# TPS61200.net
KiCad netlist of a schematic drawn in EAGLE
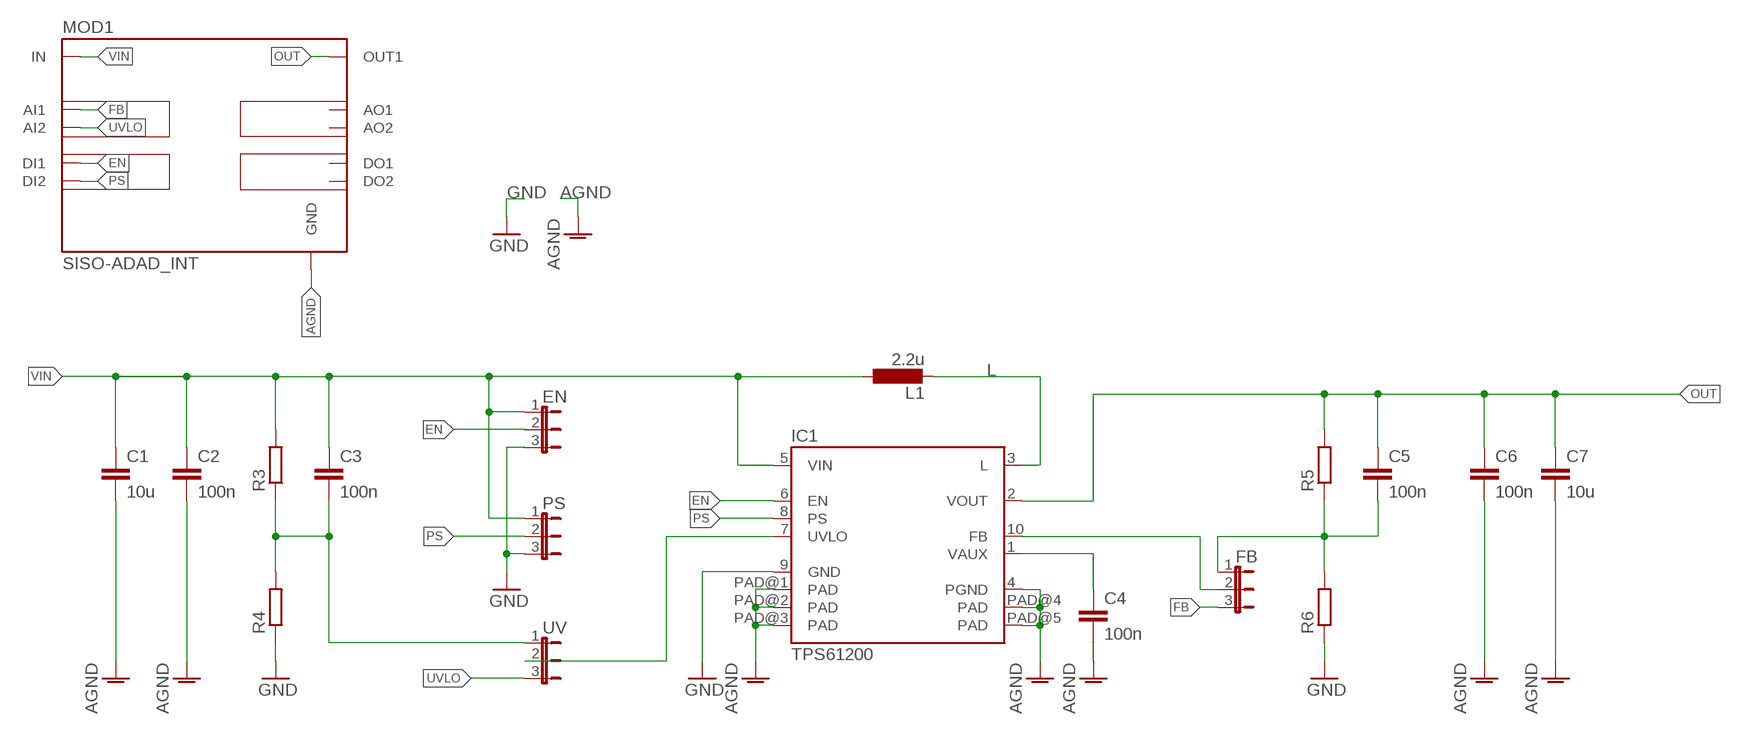
[diagram p0: schematic, sheet 1]

(export (version "E")
  (design (tool "Eeschema 10.0.6"))
  (components
    (comp (ref "C1")
      (value "10u")
      (footprint "eagle-import:C0805")
      (libsource (lib "eagle-import") (part "C-EUC0805"))
    )
    (comp (ref "C2")
      (value "100n")
      (footprint "eagle-import:C0805")
      (libsource (lib "eagle-import") (part "C-EUC0805"))
    )
    (comp (ref "C3")
      (value "100n")
      (footprint "eagle-import:C0805")
      (libsource (lib "eagle-import") (part "C-EUC0805"))
    )
    (comp (ref "C4")
      (value "100n")
      (footprint "eagle-import:C0805")
      (libsource (lib "eagle-import") (part "C-EUC0805"))
    )
    (comp (ref "C5")
      (value "100n")
      (footprint "eagle-import:C0805")
      (libsource (lib "eagle-import") (part "C-EUC0805"))
    )
    (comp (ref "C6")
      (value "100n")
      (footprint "eagle-import:C0805")
      (libsource (lib "eagle-import") (part "C-EUC0805"))
    )
    (comp (ref "C7")
      (value "10u")
      (footprint "eagle-import:C0805")
      (libsource (lib "eagle-import") (part "C-EUC0805"))
    )
    (comp (ref "EN")
      (value "JP2E")
      (footprint "eagle-import:JP2")
      (libsource (lib "eagle-import") (part "JP2E"))
    )
    (comp (ref "FB")
      (value "JP2E")
      (footprint "eagle-import:JP2")
      (libsource (lib "eagle-import") (part "JP2E"))
    )
    (comp (ref "IC1")
      (value "TPS61200")
      (footprint "eagle-import:QFN_10_PAD")
      (libsource (lib "eagle-import") (part "TPS61200"))
    )
    (comp (ref "L1")
      (value "2.2u")
      (footprint "eagle-import:L4035M")
      (libsource (lib "eagle-import") (part "L-EUL4035M"))
    )
    (comp (ref "MOD1")
      (value "SISO-ADAD_INT")
      (footprint "eagle-import:SISO-ADAD")
      (libsource (lib "eagle-import") (part "SISO-ADAD_INT"))
    )
    (comp (ref "PS")
      (value "JP2E")
      (footprint "eagle-import:JP2")
      (libsource (lib "eagle-import") (part "JP2E"))
    )
    (comp (ref "R3")
      (value "R-EU_R0805")
      (footprint "eagle-import:R0805")
      (libsource (lib "eagle-import") (part "R-EU_R0805"))
    )
    (comp (ref "R4")
      (value "R-EU_R0805")
      (footprint "eagle-import:R0805")
      (libsource (lib "eagle-import") (part "R-EU_R0805"))
    )
    (comp (ref "R5")
      (value "R-EU_R0805")
      (footprint "eagle-import:R0805")
      (libsource (lib "eagle-import") (part "R-EU_R0805"))
    )
    (comp (ref "R6")
      (value "R-EU_R0805")
      (footprint "eagle-import:R0805")
      (libsource (lib "eagle-import") (part "R-EU_R0805"))
    )
    (comp (ref "UV")
      (value "JP2E")
      (footprint "eagle-import:JP2")
      (libsource (lib "eagle-import") (part "JP2E"))
    )
  )
  (nets
    (net (code "1") (name "/L") (class "Default")
      (node (ref "IC1") (pin "3") (pinfunction "L_3") (pintype "passive"))
      (node (ref "L1") (pin "2") (pinfunction "2_2") (pintype "passive"))
    )
    (net (code "2") (name "AGND") (class "Default")
      (node (ref "C1") (pin "2") (pinfunction "2_2") (pintype "passive"))
      (node (ref "C2") (pin "2") (pinfunction "2_2") (pintype "passive"))
      (node (ref "C4") (pin "2") (pinfunction "2_2") (pintype "passive"))
      (node (ref "C6") (pin "2") (pinfunction "2_2") (pintype "passive"))
      (node (ref "C7") (pin "2") (pinfunction "2_2") (pintype "passive"))
      (node (ref "IC1") (pin "4") (pinfunction "PGND_4") (pintype "power_in"))
      (node (ref "IC1") (pin "PAD@1") (pinfunction "PAD_PAD@1") (pintype "power_in"))
      (node (ref "IC1") (pin "PAD@2") (pinfunction "PAD_PAD@2") (pintype "power_in"))
      (node (ref "IC1") (pin "PAD@3") (pinfunction "PAD_PAD@3") (pintype "power_in"))
      (node (ref "IC1") (pin "PAD@4") (pinfunction "PAD_PAD@4") (pintype "power_in"))
      (node (ref "IC1") (pin "PAD@5") (pinfunction "PAD_PAD@5") (pintype "power_in"))
      (node (ref "MOD1") (pin "GND1") (pinfunction "GND_GND1") (pintype "power_in"))
      (node (ref "MOD1") (pin "GND2") (pinfunction "GND_GND2") (pintype "power_in"))
      (node (ref "MOD1") (pin "GND3") (pinfunction "GND_GND3") (pintype "power_in"))
      (node (ref "MOD1") (pin "GND4") (pinfunction "GND_GND4") (pintype "power_in"))
    )
    (net (code "3") (name "EN") (class "Default")
      (node (ref "EN") (pin "2") (pinfunction "2_2") (pintype "passive"))
      (node (ref "IC1") (pin "6") (pinfunction "EN_6") (pintype "input"))
      (node (ref "MOD1") (pin "DI1") (pinfunction "DI1_DI1") (pintype "output"))
    )
    (net (code "4") (name "FB") (class "Default")
      (node (ref "FB") (pin "3") (pinfunction "3_3") (pintype "passive"))
      (node (ref "MOD1") (pin "AI1") (pinfunction "AI1_AI1") (pintype "output"))
    )
    (net (code "5") (name "GND") (class "Default")
      (node (ref "EN") (pin "3") (pinfunction "3_3") (pintype "passive"))
      (node (ref "IC1") (pin "9") (pinfunction "GND_9") (pintype "power_in"))
      (node (ref "PS") (pin "3") (pinfunction "3_3") (pintype "passive"))
      (node (ref "R4") (pin "1") (pinfunction "1_1") (pintype "passive"))
      (node (ref "R6") (pin "1") (pinfunction "1_1") (pintype "passive"))
    )
    (net (code "6") (name "Net-(C3-Pad2)") (class "Default")
      (node (ref "C3") (pin "2") (pinfunction "2_2") (pintype "passive"))
      (node (ref "R3") (pin "1") (pinfunction "1_1") (pintype "passive"))
      (node (ref "R4") (pin "2") (pinfunction "2_2") (pintype "passive"))
      (node (ref "UV") (pin "1") (pinfunction "1_1") (pintype "passive"))
    )
    (net (code "7") (name "Net-(C5-Pad2)") (class "Default")
      (node (ref "C5") (pin "2") (pinfunction "2_2") (pintype "passive"))
      (node (ref "FB") (pin "1") (pinfunction "1_1") (pintype "passive"))
      (node (ref "R5") (pin "1") (pinfunction "1_1") (pintype "passive"))
      (node (ref "R6") (pin "2") (pinfunction "2_2") (pintype "passive"))
    )
    (net (code "8") (name "Net-(IC1-FB)") (class "Default")
      (node (ref "FB") (pin "2") (pinfunction "2_2") (pintype "passive"))
      (node (ref "IC1") (pin "10") (pinfunction "FB_10") (pintype "passive"))
    )
    (net (code "9") (name "Net-(IC1-UVLO)") (class "Default")
      (node (ref "IC1") (pin "7") (pinfunction "UVLO_7") (pintype "passive"))
      (node (ref "UV") (pin "2") (pinfunction "2_2") (pintype "passive"))
    )
    (net (code "10") (name "Net-(IC1-VAUX)") (class "Default")
      (node (ref "C4") (pin "1") (pinfunction "1_1") (pintype "passive"))
      (node (ref "IC1") (pin "1") (pinfunction "VAUX_1") (pintype "passive"))
    )
    (net (code "11") (name "OUT") (class "Default")
      (node (ref "C5") (pin "1") (pinfunction "1_1") (pintype "passive"))
      (node (ref "C6") (pin "1") (pinfunction "1_1") (pintype "passive"))
      (node (ref "C7") (pin "1") (pinfunction "1_1") (pintype "passive"))
      (node (ref "IC1") (pin "2") (pinfunction "VOUT_2") (pintype "passive"))
      (node (ref "MOD1") (pin "OUT1_1") (pinfunction "OUT1_OUT1_1") (pintype "input"))
      (node (ref "MOD1") (pin "OUT1_2") (pinfunction "OUT1_OUT1_2") (pintype "input"))
      (node (ref "MOD1") (pin "OUT1_3") (pinfunction "OUT1_OUT1_3") (pintype "input"))
      (node (ref "MOD1") (pin "OUT1_4") (pinfunction "OUT1_OUT1_4") (pintype "input"))
      (node (ref "R5") (pin "2") (pinfunction "2_2") (pintype "passive"))
    )
    (net (code "12") (name "PS") (class "Default")
      (node (ref "IC1") (pin "8") (pinfunction "PS_8") (pintype "input"))
      (node (ref "MOD1") (pin "DI2") (pinfunction "DI2_DI2") (pintype "output"))
      (node (ref "PS") (pin "2") (pinfunction "2_2") (pintype "passive"))
    )
    (net (code "13") (name "UVLO") (class "Default")
      (node (ref "MOD1") (pin "AI2") (pinfunction "AI2_AI2") (pintype "output"))
      (node (ref "UV") (pin "3") (pinfunction "3_3") (pintype "passive"))
    )
    (net (code "14") (name "VIN") (class "Default")
      (node (ref "C1") (pin "1") (pinfunction "1_1") (pintype "passive"))
      (node (ref "C2") (pin "1") (pinfunction "1_1") (pintype "passive"))
      (node (ref "C3") (pin "1") (pinfunction "1_1") (pintype "passive"))
      (node (ref "EN") (pin "1") (pinfunction "1_1") (pintype "passive"))
      (node (ref "IC1") (pin "5") (pinfunction "VIN_5") (pintype "power_in"))
      (node (ref "L1") (pin "1") (pinfunction "1_1") (pintype "passive"))
      (node (ref "MOD1") (pin "IN1") (pinfunction "IN_IN1") (pintype "output"))
      (node (ref "MOD1") (pin "IN2") (pinfunction "IN_IN2") (pintype "output"))
      (node (ref "MOD1") (pin "IN3") (pinfunction "IN_IN3") (pintype "output"))
      (node (ref "MOD1") (pin "IN4") (pinfunction "IN_IN4") (pintype "output"))
      (node (ref "PS") (pin "1") (pinfunction "1_1") (pintype "passive"))
      (node (ref "R3") (pin "2") (pinfunction "2_2") (pintype "passive"))
    )
    (net (code "15") (name "unconnected-(MOD1-PadAO1)") (class "Default")
      (node (ref "MOD1") (pin "AO1") (pinfunction "AO1_AO1") (pintype "input"))
    )
    (net (code "16") (name "unconnected-(MOD1-PadAO2)") (class "Default")
      (node (ref "MOD1") (pin "AO2") (pinfunction "AO2_AO2") (pintype "input"))
    )
    (net (code "17") (name "unconnected-(MOD1-PadDO1)") (class "Default")
      (node (ref "MOD1") (pin "DO1") (pinfunction "DO1_DO1") (pintype "input"))
    )
    (net (code "18") (name "unconnected-(MOD1-PadDO2)") (class "Default")
      (node (ref "MOD1") (pin "DO2") (pinfunction "DO2_DO2") (pintype "input"))
    )
  )
)
